# power.net
KiCad netlist of a schematic drawn in Altium Designer
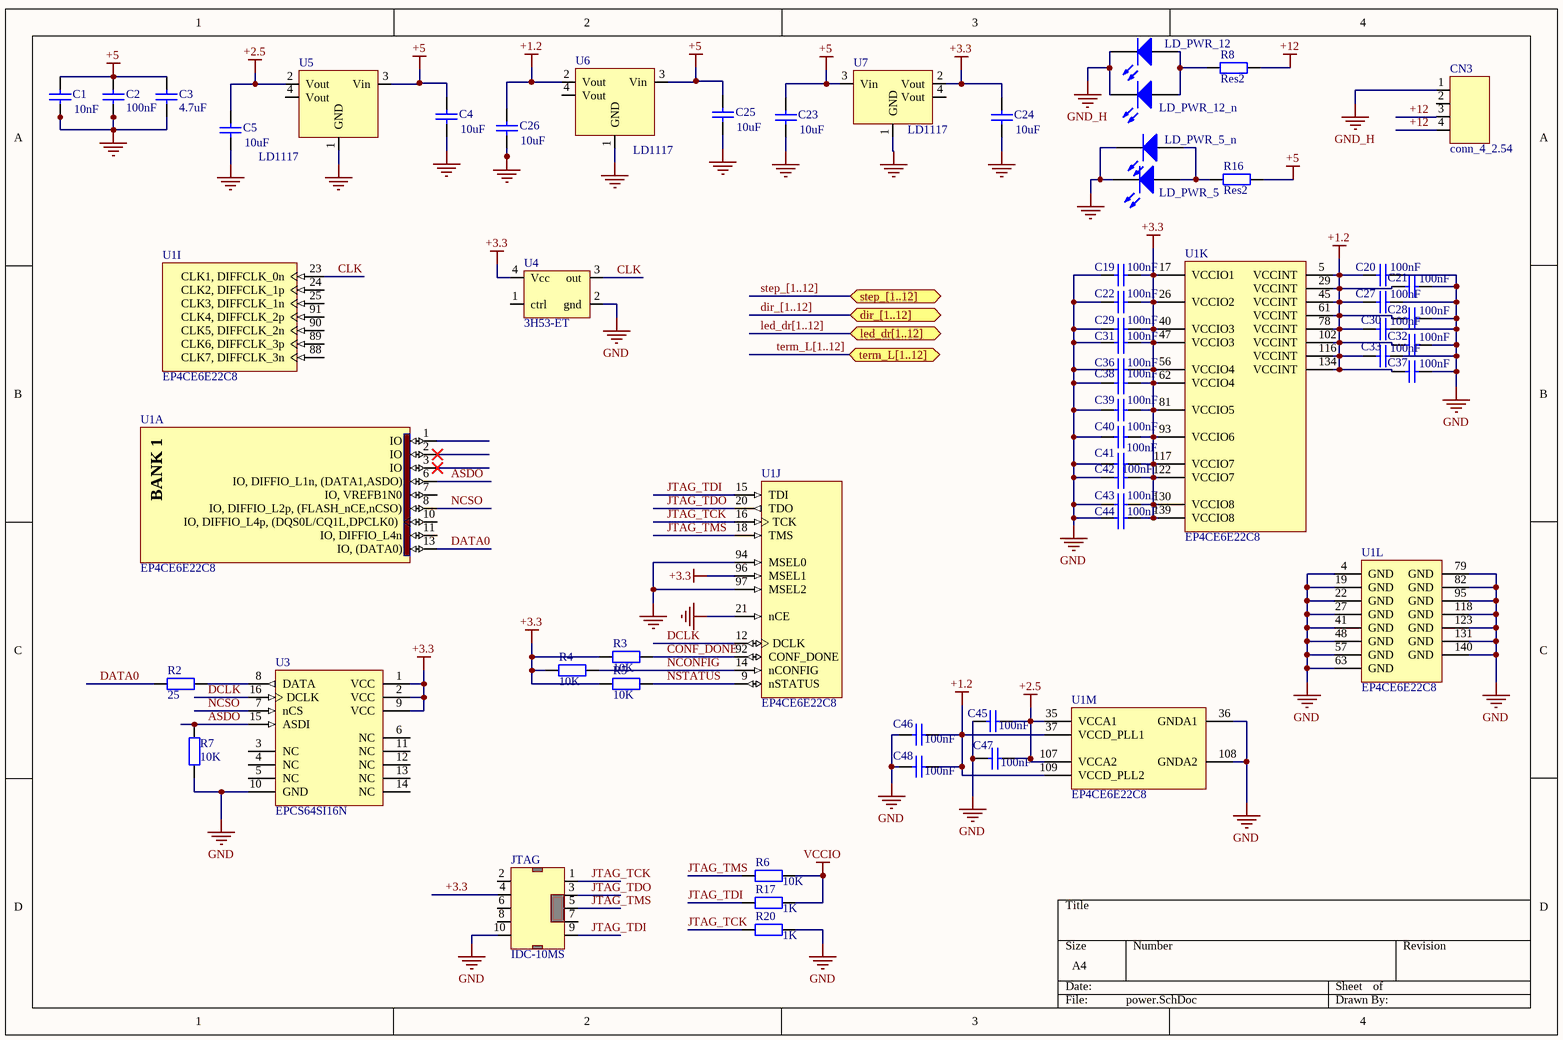
[diagram p0: power.SchDoc]

(export (version "E")
  (design (tool "Eeschema 10.0.6"))
  (components
    (comp (ref "C1")
      (value "10nF")
      (footprint "CAPC1608M")
      (description "Capacitor")
      (fields (field (name "Comment") "Cap") (field (name "PUBLISHER") "Altium Limited"))
      (libsource (lib "Miscellaneous Devices") (part "Cap"))
    )
    (comp (ref "C2")
      (value "100nF")
      (footprint "CAPC1608M")
      (description "Capacitor")
      (fields (field (name "Comment") "Cap") (field (name "PUBLISHER") "Altium Limited"))
      (libsource (lib "Miscellaneous Devices") (part "Cap"))
    )
    (comp (ref "C3")
      (value "4.7uF")
      (footprint "CAPC1608M")
      (description "Capacitor")
      (fields (field (name "Comment") "Cap") (field (name "PUBLISHER") "Altium Limited"))
      (libsource (lib "Miscellaneous Devices") (part "Cap"))
    )
    (comp (ref "C4")
      (value "10uF")
      (footprint "CAPC2012M")
      (description "Capacitor")
      (fields (field (name "Comment") "Cap") (field (name "PUBLISHER") "Altium Limited"))
      (libsource (lib "Miscellaneous Devices") (part "Cap"))
    )
    (comp (ref "C5")
      (value "10uF")
      (footprint "CAPC2012M")
      (description "Capacitor")
      (fields (field (name "Comment") "Cap") (field (name "PUBLISHER") "Altium Limited"))
      (libsource (lib "Miscellaneous Devices") (part "Cap"))
    )
    (comp (ref "C19")
      (value "100nF")
      (footprint "CAPC1608M")
      (description "Capacitor")
      (fields (field (name "Comment") "Cap") (field (name "PUBLISHER") "Altium Limited"))
      (libsource (lib "Miscellaneous Devices") (part "Cap"))
    )
    (comp (ref "C20")
      (value "100nF")
      (footprint "CAPC1608M")
      (description "Capacitor")
      (fields (field (name "Comment") "Cap") (field (name "PUBLISHER") "Altium Limited"))
      (libsource (lib "Miscellaneous Devices") (part "Cap"))
    )
    (comp (ref "C21")
      (value "100nF")
      (footprint "CAPC1608M")
      (description "Capacitor")
      (fields (field (name "Comment") "Cap") (field (name "PUBLISHER") "Altium Limited"))
      (libsource (lib "Miscellaneous Devices") (part "Cap"))
    )
    (comp (ref "C22")
      (value "100nF")
      (footprint "CAPC1608M")
      (description "Capacitor")
      (fields (field (name "Comment") "Cap") (field (name "PUBLISHER") "Altium Limited"))
      (libsource (lib "Miscellaneous Devices") (part "Cap"))
    )
    (comp (ref "C23")
      (value "10uF")
      (footprint "CAPC2012M")
      (description "Capacitor")
      (fields (field (name "Comment") "Cap") (field (name "PUBLISHER") "Altium Limited"))
      (libsource (lib "Miscellaneous Devices") (part "Cap"))
    )
    (comp (ref "C24")
      (value "10uF")
      (footprint "CAPC2012M")
      (description "Capacitor")
      (fields (field (name "Comment") "Cap") (field (name "PUBLISHER") "Altium Limited"))
      (libsource (lib "Miscellaneous Devices") (part "Cap"))
    )
    (comp (ref "C25")
      (value "10uF")
      (footprint "CAPC2012M")
      (description "Capacitor")
      (fields (field (name "Comment") "Cap") (field (name "PUBLISHER") "Altium Limited"))
      (libsource (lib "Miscellaneous Devices") (part "Cap"))
    )
    (comp (ref "C26")
      (value "10uF")
      (footprint "CAPC2012M")
      (description "Capacitor")
      (fields (field (name "Comment") "Cap") (field (name "PUBLISHER") "Altium Limited"))
      (libsource (lib "Miscellaneous Devices") (part "Cap"))
    )
    (comp (ref "C27")
      (value "100nF")
      (footprint "CAPC1608M")
      (description "Capacitor")
      (fields (field (name "Comment") "Cap") (field (name "PUBLISHER") "Altium Limited"))
      (libsource (lib "Miscellaneous Devices") (part "Cap"))
    )
    (comp (ref "C28")
      (value "100nF")
      (footprint "CAPC1608M")
      (description "Capacitor")
      (fields (field (name "Comment") "Cap") (field (name "PUBLISHER") "Altium Limited"))
      (libsource (lib "Miscellaneous Devices") (part "Cap"))
    )
    (comp (ref "C29")
      (value "100nF")
      (footprint "CAPC1608M")
      (description "Capacitor")
      (fields (field (name "Comment") "Cap") (field (name "PUBLISHER") "Altium Limited"))
      (libsource (lib "Miscellaneous Devices") (part "Cap"))
    )
    (comp (ref "C30")
      (value "100nF")
      (footprint "CAPC1608M")
      (description "Capacitor")
      (fields (field (name "Comment") "Cap") (field (name "PUBLISHER") "Altium Limited"))
      (libsource (lib "Miscellaneous Devices") (part "Cap"))
    )
    (comp (ref "C31")
      (value "100nF")
      (footprint "CAPC1608M")
      (description "Capacitor")
      (fields (field (name "Comment") "Cap") (field (name "PUBLISHER") "Altium Limited"))
      (libsource (lib "Miscellaneous Devices") (part "Cap"))
    )
    (comp (ref "C32")
      (value "100nF")
      (footprint "CAPC1608M")
      (description "Capacitor")
      (fields (field (name "Comment") "Cap") (field (name "PUBLISHER") "Altium Limited"))
      (libsource (lib "Miscellaneous Devices") (part "Cap"))
    )
    (comp (ref "C33")
      (value "100nF")
      (footprint "CAPC1608M")
      (description "Capacitor")
      (fields (field (name "Comment") "Cap") (field (name "PUBLISHER") "Altium Limited"))
      (libsource (lib "Miscellaneous Devices") (part "Cap"))
    )
    (comp (ref "C36")
      (value "100nF")
      (footprint "CAPC1608M")
      (description "Capacitor")
      (fields (field (name "Comment") "Cap") (field (name "PUBLISHER") "Altium Limited"))
      (libsource (lib "Miscellaneous Devices") (part "Cap"))
    )
    (comp (ref "C37")
      (value "100nF")
      (footprint "CAPC1608M")
      (description "Capacitor")
      (fields (field (name "Comment") "Cap") (field (name "PUBLISHER") "Altium Limited"))
      (libsource (lib "Miscellaneous Devices") (part "Cap"))
    )
    (comp (ref "C38")
      (value "100nF")
      (footprint "CAPC1608M")
      (description "Capacitor")
      (fields (field (name "Comment") "Cap") (field (name "PUBLISHER") "Altium Limited"))
      (libsource (lib "Miscellaneous Devices") (part "Cap"))
    )
    (comp (ref "C39")
      (value "100nF")
      (footprint "CAPC1608M")
      (description "Capacitor")
      (fields (field (name "Comment") "Cap") (field (name "PUBLISHER") "Altium Limited"))
      (libsource (lib "Miscellaneous Devices") (part "Cap"))
    )
    (comp (ref "C40")
      (value "100nF")
      (footprint "CAPC1608M")
      (description "Capacitor")
      (fields (field (name "Comment") "Cap") (field (name "PUBLISHER") "Altium Limited"))
      (libsource (lib "Miscellaneous Devices") (part "Cap"))
    )
    (comp (ref "C41")
      (value "100nF")
      (footprint "CAPC1608M")
      (description "Capacitor")
      (fields (field (name "Comment") "Cap") (field (name "PUBLISHER") "Altium Limited"))
      (libsource (lib "Miscellaneous Devices") (part "Cap"))
    )
    (comp (ref "C42")
      (value "100nF")
      (footprint "CAPC1608M")
      (description "Capacitor")
      (fields (field (name "Comment") "Cap") (field (name "PUBLISHER") "Altium Limited"))
      (libsource (lib "Miscellaneous Devices") (part "Cap"))
    )
    (comp (ref "C43")
      (value "100nF")
      (footprint "CAPC1608M")
      (description "Capacitor")
      (fields (field (name "Comment") "Cap") (field (name "PUBLISHER") "Altium Limited"))
      (libsource (lib "Miscellaneous Devices") (part "Cap"))
    )
    (comp (ref "C44")
      (value "100nF")
      (footprint "CAPC1608M")
      (description "Capacitor")
      (fields (field (name "Comment") "Cap") (field (name "PUBLISHER") "Altium Limited"))
      (libsource (lib "Miscellaneous Devices") (part "Cap"))
    )
    (comp (ref "C45")
      (value "100nF")
      (footprint "CAPC1608M")
      (description "Capacitor")
      (fields (field (name "Comment") "Cap") (field (name "PUBLISHER") "Altium Limited"))
      (libsource (lib "Miscellaneous Devices") (part "Cap"))
    )
    (comp (ref "C46")
      (value "100nF")
      (footprint "CAPC1608M")
      (description "Capacitor")
      (fields (field (name "Comment") "Cap") (field (name "PUBLISHER") "Altium Limited"))
      (libsource (lib "Miscellaneous Devices") (part "Cap"))
    )
    (comp (ref "C47")
      (value "100nF")
      (footprint "CAPC1608M")
      (description "Capacitor")
      (fields (field (name "Comment") "Cap") (field (name "PUBLISHER") "Altium Limited"))
      (libsource (lib "Miscellaneous Devices") (part "Cap"))
    )
    (comp (ref "C48")
      (value "100nF")
      (footprint "CAPC1608M")
      (description "Capacitor")
      (fields (field (name "Comment") "Cap") (field (name "PUBLISHER") "Altium Limited"))
      (libsource (lib "Miscellaneous Devices") (part "Cap"))
    )
    (comp (ref "CN3")
      (value "conn_4_2.54")
      (footprint "SCKT/SM4.5-2H4")
      (libsource (lib "Schlib1") (part "conn_4_2.54"))
    )
    (comp (ref "JTAG")
      (value "IDC-10MS")
      (footprint "IDC2.54-V10D")
      (description "BH-10(IDC-10MS)")
      (libsource (lib "IDC") (part "BH-10(IDC-10MS)"))
    )
    (comp (ref "LD_PWR_5")
      (value "led")
      (footprint "RESC2012M")
      (description "chip led")
      (libsource (lib "Schlib1") (part "chip led"))
    )
    (comp (ref "LD_PWR_5_n")
      (value "led")
      (footprint "led-pins")
      (description "chip led")
      (libsource (lib "Schlib1") (part "chip led"))
    )
    (comp (ref "LD_PWR_12")
      (value "led")
      (footprint "RESC2012M")
      (description "chip led")
      (libsource (lib "Schlib1") (part "chip led"))
    )
    (comp (ref "LD_PWR_12_n")
      (value "led")
      (footprint "led-pins")
      (description "chip led")
      (libsource (lib "Schlib1") (part "chip led"))
    )
    (comp (ref "R2")
      (value "25")
      (footprint "RESC2012M")
      (description "Resistor")
      (fields (field (name "PUBLISHER") "Altium Limited"))
      (libsource (lib "Miscellaneous Devices") (part "Res2"))
    )
    (comp (ref "R3")
      (value "10K")
      (footprint "RESC2012M")
      (description "Resistor")
      (fields (field (name "PUBLISHER") "Altium Limited"))
      (libsource (lib "Miscellaneous Devices") (part "Res2"))
    )
    (comp (ref "R4")
      (value "10K")
      (footprint "RESC2012M")
      (description "Resistor")
      (fields (field (name "PUBLISHER") "Altium Limited"))
      (libsource (lib "Miscellaneous Devices") (part "Res2"))
    )
    (comp (ref "R5")
      (value "10K")
      (footprint "RESC2012M")
      (description "Resistor")
      (fields (field (name "PUBLISHER") "Altium Limited"))
      (libsource (lib "Miscellaneous Devices") (part "Res2"))
    )
    (comp (ref "R6")
      (value "10K")
      (footprint "RESC2012M")
      (description "Resistor")
      (fields (field (name "PUBLISHER") "Altium Limited"))
      (libsource (lib "Miscellaneous Devices") (part "Res2"))
    )
    (comp (ref "R7")
      (value "10K")
      (footprint "RESC2012M")
      (description "Resistor")
      (fields (field (name "Comment") "Res2") (field (name "PUBLISHER") "Altium Limited"))
      (libsource (lib "Miscellaneous Devices") (part "Res2"))
    )
    (comp (ref "R8")
      (value "Res2")
      (footprint "RESC2012M")
      (description "Resistor")
      (fields (field (name "PUBLISHER") "Altium Limited"))
      (libsource (lib "Miscellaneous Devices") (part "Res2"))
    )
    (comp (ref "R16")
      (value "Res2")
      (footprint "RESC2012M")
      (description "Resistor")
      (fields (field (name "PUBLISHER") "Altium Limited"))
      (libsource (lib "Miscellaneous Devices") (part "Res2"))
    )
    (comp (ref "R17")
      (value "1K")
      (footprint "RESC2012M")
      (description "Resistor")
      (fields (field (name "PUBLISHER") "Altium Limited"))
      (libsource (lib "Miscellaneous Devices") (part "Res2"))
    )
    (comp (ref "R20")
      (value "1K")
      (footprint "RESC2012M")
      (description "Resistor")
      (fields (field (name "PUBLISHER") "Altium Limited"))
      (libsource (lib "Miscellaneous Devices") (part "Res2"))
    )
    (comp (ref "U1")
      (value "EP4CE6E22C8")
      (footprint "EQFP144_M")
      (description "Cyclone IV Family FPGA, 2V Core, 91 I/O Pins, 2 PLLs, 144-Pin QFP, Speed Grade 8, Commercial Grade")
      (fields (field (name "PUBLISHER") "Altium Limited"))
      (libsource (lib "Altera Cyclone IV E") (part "EP4CE6E22C8"))
    )
    (comp (ref "U3")
      (value "EPCS64SI16N")
      (footprint "SOIC16_M")
      (fields (field (name "PUBLISHER") "Altium Limited"))
      (libsource (lib "Altera EPCS Configuration Device") (part "EPCS64SI16N"))
    )
    (comp (ref "U4")
      (value "3H53-ET")
      (footprint "2SMX-3SMXB")
      (description "Кварцевый генератор")
      (libsource (lib "Schlib1") (part "3H53-ET"))
    )
    (comp (ref "U5")
      (value "LD1117")
      (footprint "SOT223-4M")
      (description "st LD1086D2T")
      (libsource (lib "Schlib1") (part "LD1086D2T"))
    )
    (comp (ref "U6")
      (value "LD1117")
      (footprint "SOT223-4M")
      (description "st LD1086D2T")
      (libsource (lib "Schlib1") (part "LD1086D2T"))
    )
    (comp (ref "U7")
      (value "LD1117")
      (footprint "SOT223-4M")
      (description "ADP3339AKCZ-3.3-R7")
      (libsource (lib "Schlib1") (part "ADP3339"))
    )
  )
  (nets
    (net (code "49") (name "+1.2") (class "Default")
      (node (ref "C20") (pin "1") (pinfunction "1_1") (pintype "passive"))
      (node (ref "C21") (pin "1") (pinfunction "1_1") (pintype "passive"))
      (node (ref "C26") (pin "1") (pinfunction "1_1") (pintype "passive"))
      (node (ref "C27") (pin "1") (pinfunction "1_1") (pintype "passive"))
      (node (ref "C28") (pin "1") (pinfunction "1_1") (pintype "passive"))
      (node (ref "C30") (pin "1") (pinfunction "1_1") (pintype "passive"))
      (node (ref "C32") (pin "1") (pinfunction "1_1") (pintype "passive"))
      (node (ref "C33") (pin "1") (pinfunction "1_1") (pintype "passive"))
      (node (ref "C37") (pin "1") (pinfunction "1_1") (pintype "passive"))
      (node (ref "C46") (pin "2") (pinfunction "2_2") (pintype "passive"))
      (node (ref "C48") (pin "2") (pinfunction "2_2") (pintype "passive"))
      (node (ref "U1") (pin "102") (pinfunction "VCCINT_102") (pintype "power_in"))
      (node (ref "U1") (pin "109") (pinfunction "VCCD_PLL2_109") (pintype "power_in"))
      (node (ref "U1") (pin "116") (pinfunction "VCCINT_116") (pintype "power_in"))
      (node (ref "U1") (pin "134") (pinfunction "VCCINT_134") (pintype "power_in"))
      (node (ref "U1") (pin "29") (pinfunction "VCCINT_29") (pintype "power_in"))
      (node (ref "U1") (pin "37") (pinfunction "VCCD_PLL1_37") (pintype "power_in"))
      (node (ref "U1") (pin "45") (pinfunction "VCCINT_45") (pintype "power_in"))
      (node (ref "U1") (pin "5") (pinfunction "VCCINT_5") (pintype "power_in"))
      (node (ref "U1") (pin "61") (pinfunction "VCCINT_61") (pintype "power_in"))
      (node (ref "U1") (pin "78") (pinfunction "VCCINT_78") (pintype "power_in"))
      (node (ref "U6") (pin "2") (pinfunction "Vout_2") (pintype "passive"))
    )
    (net (code "50") (name "+2.5") (class "Default")
      (node (ref "C45") (pin "2") (pinfunction "2_2") (pintype "passive"))
      (node (ref "C47") (pin "2") (pinfunction "2_2") (pintype "passive"))
      (node (ref "C5") (pin "1") (pinfunction "1_1") (pintype "passive"))
      (node (ref "U1") (pin "107") (pinfunction "VCCA2_107") (pintype "power_in"))
      (node (ref "U1") (pin "35") (pinfunction "VCCA1_35") (pintype "power_in"))
      (node (ref "U5") (pin "2") (pinfunction "Vout_2") (pintype "passive"))
    )
    (net (code "51") (name "+3.3") (class "Default")
      (node (ref "C19") (pin "2") (pinfunction "2_2") (pintype "passive"))
      (node (ref "C22") (pin "2") (pinfunction "2_2") (pintype "passive"))
      (node (ref "C24") (pin "1") (pinfunction "1_1") (pintype "passive"))
      (node (ref "C29") (pin "2") (pinfunction "2_2") (pintype "passive"))
      (node (ref "C31") (pin "2") (pinfunction "2_2") (pintype "passive"))
      (node (ref "C36") (pin "2") (pinfunction "2_2") (pintype "passive"))
      (node (ref "C38") (pin "2") (pinfunction "2_2") (pintype "passive"))
      (node (ref "C39") (pin "2") (pinfunction "2_2") (pintype "passive"))
      (node (ref "C40") (pin "2") (pinfunction "2_2") (pintype "passive"))
      (node (ref "C41") (pin "2") (pinfunction "2_2") (pintype "passive"))
      (node (ref "C42") (pin "2") (pinfunction "2_2") (pintype "passive"))
      (node (ref "C43") (pin "2") (pinfunction "2_2") (pintype "passive"))
      (node (ref "C44") (pin "2") (pinfunction "2_2") (pintype "passive"))
      (node (ref "JTAG") (pin "4") (pintype "passive"))
      (node (ref "R3") (pin "1") (pinfunction "1_1") (pintype "passive"))
      (node (ref "R4") (pin "1") (pinfunction "1_1") (pintype "passive"))
      (node (ref "R5") (pin "1") (pinfunction "1_1") (pintype "passive"))
      (node (ref "U1") (pin "117") (pinfunction "VCCIO7_117") (pintype "power_in"))
      (node (ref "U1") (pin "122") (pinfunction "VCCIO7_122") (pintype "power_in"))
      (node (ref "U1") (pin "130") (pinfunction "VCCIO8_130") (pintype "power_in"))
      (node (ref "U1") (pin "139") (pinfunction "VCCIO8_139") (pintype "power_in"))
      (node (ref "U1") (pin "17") (pinfunction "VCCIO1_17") (pintype "power_in"))
      (node (ref "U1") (pin "26") (pinfunction "VCCIO2_26") (pintype "power_in"))
      (node (ref "U1") (pin "40") (pinfunction "VCCIO3_40") (pintype "power_in"))
      (node (ref "U1") (pin "47") (pinfunction "VCCIO3_47") (pintype "power_in"))
      (node (ref "U1") (pin "56") (pinfunction "VCCIO4_56") (pintype "power_in"))
      (node (ref "U1") (pin "62") (pinfunction "VCCIO4_62") (pintype "power_in"))
      (node (ref "U1") (pin "81") (pinfunction "VCCIO5_81") (pintype "power_in"))
      (node (ref "U1") (pin "93") (pinfunction "VCCIO6_93") (pintype "power_in"))
      (node (ref "U1") (pin "96") (pinfunction "MSEL1_96") (pintype "input"))
      (node (ref "U3") (pin "1") (pinfunction "VCC_1") (pintype "power_in"))
      (node (ref "U3") (pin "2") (pinfunction "VCC_2") (pintype "power_in"))
      (node (ref "U3") (pin "9") (pinfunction "VCC_9") (pintype "power_in"))
      (node (ref "U4") (pin "4") (pinfunction "Vcc_4") (pintype "passive"))
      (node (ref "U7") (pin "2") (pinfunction "Vout_2") (pintype "power_in"))
    )
    (net (code "52") (name "+5") (class "Default")
      (node (ref "C1") (pin "1") (pinfunction "1_1") (pintype "passive"))
      (node (ref "C2") (pin "1") (pinfunction "1_1") (pintype "passive"))
      (node (ref "C23") (pin "1") (pinfunction "1_1") (pintype "passive"))
      (node (ref "C25") (pin "1") (pinfunction "1_1") (pintype "passive"))
      (node (ref "C3") (pin "1") (pinfunction "1_1") (pintype "passive"))
      (node (ref "C4") (pin "1") (pinfunction "1_1") (pintype "passive"))
      (node (ref "R16") (pin "2") (pinfunction "2_2") (pintype "passive"))
      (node (ref "U5") (pin "3") (pinfunction "Vin_3") (pintype "passive"))
      (node (ref "U6") (pin "3") (pinfunction "Vin_3") (pintype "passive"))
      (node (ref "U7") (pin "3") (pinfunction "Vin_3") (pintype "power_in"))
    )
    (net (code "53") (name "+12") (class "Default")
      (node (ref "CN3") (pin "3") (pintype "passive"))
      (node (ref "CN3") (pin "4") (pintype "passive"))
      (node (ref "R8") (pin "2") (pinfunction "2_2") (pintype "passive"))
    )
    (net (code "54") (name "/ASDO") (class "Default")
      (node (ref "R7") (pin "2") (pinfunction "2_2") (pintype "passive"))
      (node (ref "U1") (pin "6") (pinfunction "IO,_DIFFIO_L1n,_(DATA1,ASDO)_6") (pintype "bidirectional"))
      (node (ref "U3") (pin "15") (pinfunction "ASDI_15") (pintype "input"))
    )
    (net (code "55") (name "/CLK") (class "Default")
      (node (ref "U1") (pin "23") (pinfunction "CLK1,_DIFFCLK_0n_23") (pintype "input"))
      (node (ref "U4") (pin "3") (pinfunction "out_3") (pintype "passive"))
    )
    (net (code "56") (name "/CONF_DONE") (class "Default")
      (node (ref "R3") (pin "2") (pinfunction "2_2") (pintype "passive"))
      (node (ref "U1") (pin "92") (pinfunction "CONF_DONE_92") (pintype "bidirectional"))
    )
    (net (code "57") (name "/DATA0") (class "Default")
      (node (ref "R2") (pin "1") (pinfunction "1_1") (pintype "passive"))
      (node (ref "U1") (pin "13") (pinfunction "IO,_(DATA0)_13") (pintype "bidirectional"))
    )
    (net (code "58") (name "/DCLK") (class "Default")
      (node (ref "U1") (pin "12") (pinfunction "DCLK_12") (pintype "bidirectional"))
      (node (ref "U3") (pin "16") (pinfunction "DCLK_16") (pintype "input"))
    )
    (net (code "59") (name "/JTAG_TCK") (class "Default")
      (node (ref "JTAG") (pin "1") (pintype "passive"))
      (node (ref "R20") (pin "1") (pinfunction "1_1") (pintype "passive"))
      (node (ref "U1") (pin "16") (pinfunction "TCK_16") (pintype "input"))
    )
    (net (code "60") (name "/JTAG_TDI") (class "Default")
      (node (ref "JTAG") (pin "9") (pintype "passive"))
      (node (ref "R17") (pin "1") (pinfunction "1_1") (pintype "passive"))
      (node (ref "U1") (pin "15") (pinfunction "TDI_15") (pintype "input"))
    )
    (net (code "61") (name "/JTAG_TDO") (class "Default")
      (node (ref "JTAG") (pin "3") (pintype "passive"))
      (node (ref "U1") (pin "20") (pinfunction "TDO_20") (pintype "output"))
    )
    (net (code "62") (name "/JTAG_TMS") (class "Default")
      (node (ref "JTAG") (pin "5") (pintype "passive"))
      (node (ref "R6") (pin "1") (pinfunction "1_1") (pintype "passive"))
      (node (ref "U1") (pin "18") (pinfunction "TMS_18") (pintype "input"))
    )
    (net (code "63") (name "/NCONFIG") (class "Default")
      (node (ref "R4") (pin "2") (pinfunction "2_2") (pintype "passive"))
      (node (ref "U1") (pin "14") (pinfunction "nCONFIG_14") (pintype "input"))
    )
    (net (code "64") (name "/NCSO") (class "Default")
      (node (ref "U1") (pin "8") (pinfunction "IO,_DIFFIO_L2p,_(FLASH_nCE,nCSO)_8") (pintype "bidirectional"))
      (node (ref "U3") (pin "7") (pinfunction "nCS_7") (pintype "input"))
    )
    (net (code "65") (name "/NSTATUS") (class "Default")
      (node (ref "R5") (pin "2") (pinfunction "2_2") (pintype "passive"))
      (node (ref "U1") (pin "9") (pinfunction "nSTATUS_9") (pintype "bidirectional"))
    )
    (net (code "70") (name "GND") (class "Default")
      (node (ref "C1") (pin "2") (pinfunction "2_2") (pintype "passive"))
      (node (ref "C19") (pin "1") (pinfunction "1_1") (pintype "passive"))
      (node (ref "C2") (pin "2") (pinfunction "2_2") (pintype "passive"))
      (node (ref "C20") (pin "2") (pinfunction "2_2") (pintype "passive"))
      (node (ref "C21") (pin "2") (pinfunction "2_2") (pintype "passive"))
      (node (ref "C22") (pin "1") (pinfunction "1_1") (pintype "passive"))
      (node (ref "C23") (pin "2") (pinfunction "2_2") (pintype "passive"))
      (node (ref "C24") (pin "2") (pinfunction "2_2") (pintype "passive"))
      (node (ref "C25") (pin "2") (pinfunction "2_2") (pintype "passive"))
      (node (ref "C26") (pin "2") (pinfunction "2_2") (pintype "passive"))
      (node (ref "C27") (pin "2") (pinfunction "2_2") (pintype "passive"))
      (node (ref "C28") (pin "2") (pinfunction "2_2") (pintype "passive"))
      (node (ref "C29") (pin "1") (pinfunction "1_1") (pintype "passive"))
      (node (ref "C3") (pin "2") (pinfunction "2_2") (pintype "passive"))
      (node (ref "C30") (pin "2") (pinfunction "2_2") (pintype "passive"))
      (node (ref "C31") (pin "1") (pinfunction "1_1") (pintype "passive"))
      (node (ref "C32") (pin "2") (pinfunction "2_2") (pintype "passive"))
      (node (ref "C33") (pin "2") (pinfunction "2_2") (pintype "passive"))
      (node (ref "C36") (pin "1") (pinfunction "1_1") (pintype "passive"))
      (node (ref "C37") (pin "2") (pinfunction "2_2") (pintype "passive"))
      (node (ref "C38") (pin "1") (pinfunction "1_1") (pintype "passive"))
      (node (ref "C39") (pin "1") (pinfunction "1_1") (pintype "passive"))
      (node (ref "C4") (pin "2") (pinfunction "2_2") (pintype "passive"))
      (node (ref "C40") (pin "1") (pinfunction "1_1") (pintype "passive"))
      (node (ref "C41") (pin "1") (pinfunction "1_1") (pintype "passive"))
      (node (ref "C42") (pin "1") (pinfunction "1_1") (pintype "passive"))
      (node (ref "C43") (pin "1") (pinfunction "1_1") (pintype "passive"))
      (node (ref "C44") (pin "1") (pinfunction "1_1") (pintype "passive"))
      (node (ref "C45") (pin "1") (pinfunction "1_1") (pintype "passive"))
      (node (ref "C46") (pin "1") (pinfunction "1_1") (pintype "passive"))
      (node (ref "C47") (pin "1") (pinfunction "1_1") (pintype "passive"))
      (node (ref "C48") (pin "1") (pinfunction "1_1") (pintype "passive"))
      (node (ref "C5") (pin "2") (pinfunction "2_2") (pintype "passive"))
      (node (ref "JTAG") (pin "10") (pintype "passive"))
      (node (ref "LD_PWR_5") (pin "2") (pinfunction "K_2") (pintype "passive"))
      (node (ref "LD_PWR_5_n") (pin "2") (pinfunction "K_2") (pintype "passive"))
      (node (ref "R20") (pin "2") (pinfunction "2_2") (pintype "passive"))
      (node (ref "R7") (pin "1") (pinfunction "1_1") (pintype "passive"))
      (node (ref "U1") (pin "108") (pinfunction "GNDA2_108") (pintype "power_in"))
      (node (ref "U1") (pin "118") (pinfunction "GND_118") (pintype "power_in"))
      (node (ref "U1") (pin "123") (pinfunction "GND_123") (pintype "power_in"))
      (node (ref "U1") (pin "131") (pinfunction "GND_131") (pintype "power_in"))
      (node (ref "U1") (pin "140") (pinfunction "GND_140") (pintype "power_in"))
      (node (ref "U1") (pin "19") (pinfunction "GND_19") (pintype "power_in"))
      (node (ref "U1") (pin "21") (pinfunction "nCE_21") (pintype "input"))
      (node (ref "U1") (pin "22") (pinfunction "GND_22") (pintype "power_in"))
      (node (ref "U1") (pin "27") (pinfunction "GND_27") (pintype "power_in"))
      (node (ref "U1") (pin "36") (pinfunction "GNDA1_36") (pintype "power_in"))
      (node (ref "U1") (pin "4") (pinfunction "GND_4") (pintype "power_in"))
      (node (ref "U1") (pin "41") (pinfunction "GND_41") (pintype "power_in"))
      (node (ref "U1") (pin "48") (pinfunction "GND_48") (pintype "power_in"))
      (node (ref "U1") (pin "57") (pinfunction "GND_57") (pintype "power_in"))
      (node (ref "U1") (pin "63") (pinfunction "GND_63") (pintype "power_in"))
      (node (ref "U1") (pin "79") (pinfunction "GND_79") (pintype "power_in"))
      (node (ref "U1") (pin "82") (pinfunction "GND_82") (pintype "power_in"))
      (node (ref "U1") (pin "94") (pinfunction "MSEL0_94") (pintype "input"))
      (node (ref "U1") (pin "95") (pinfunction "GND_95") (pintype "power_in"))
      (node (ref "U1") (pin "97") (pinfunction "MSEL2_97") (pintype "input"))
      (node (ref "U3") (pin "10") (pinfunction "GND_10") (pintype "power_in"))
      (node (ref "U4") (pin "2") (pinfunction "gnd_2") (pintype "passive"))
      (node (ref "U5") (pin "1") (pinfunction "GND_1") (pintype "passive"))
      (node (ref "U6") (pin "1") (pinfunction "GND_1") (pintype "passive"))
      (node (ref "U7") (pin "1") (pinfunction "GND_1") (pintype "power_in"))
    )
    (net (code "71") (name "GND_H") (class "Default")
      (node (ref "CN3") (pin "1") (pintype "passive"))
      (node (ref "LD_PWR_12") (pin "2") (pinfunction "K_2") (pintype "passive"))
      (node (ref "LD_PWR_12_n") (pin "2") (pinfunction "K_2") (pintype "passive"))
    )
    (net (code "72") (name "Net-(LD_PWR_5-A)") (class "Default")
      (node (ref "LD_PWR_5") (pin "1") (pinfunction "A_1") (pintype "passive"))
      (node (ref "LD_PWR_5_n") (pin "1") (pinfunction "A_1") (pintype "passive"))
      (node (ref "R16") (pin "1") (pinfunction "1_1") (pintype "passive"))
    )
    (net (code "73") (name "Net-(LD_PWR_12-A)") (class "Default")
      (node (ref "LD_PWR_12") (pin "1") (pinfunction "A_1") (pintype "passive"))
      (node (ref "LD_PWR_12_n") (pin "1") (pinfunction "A_1") (pintype "passive"))
      (node (ref "R8") (pin "1") (pinfunction "1_1") (pintype "passive"))
    )
    (net (code "74") (name "Net-(U3-DATA)") (class "Default")
      (node (ref "R2") (pin "2") (pinfunction "2_2") (pintype "passive"))
      (node (ref "U3") (pin "8") (pinfunction "DATA_8") (pintype "output"))
    )
    (net (code "75") (name "VCCIO") (class "Default")
      (node (ref "R17") (pin "2") (pinfunction "2_2") (pintype "passive"))
      (node (ref "R6") (pin "2") (pinfunction "2_2") (pintype "passive"))
    )
    (net (code "76") (name "unconnected-(CN3-Pad2)") (class "Default")
      (node (ref "CN3") (pin "2") (pintype "passive"))
    )
    (net (code "77") (name "unconnected-(JTAG-Pad2)") (class "Default")
      (node (ref "JTAG") (pin "2") (pintype "passive"))
    )
    (net (code "78") (name "unconnected-(JTAG-Pad6)") (class "Default")
      (node (ref "JTAG") (pin "6") (pintype "passive"))
    )
    (net (code "79") (name "unconnected-(JTAG-Pad7)") (class "Default")
      (node (ref "JTAG") (pin "7") (pintype "passive"))
    )
    (net (code "80") (name "unconnected-(JTAG-Pad8)") (class "Default")
      (node (ref "JTAG") (pin "8") (pintype "passive"))
    )
    (net (code "81") (name "unconnected-(U1A-IO,_DIFFIO_L4n-Pad11)") (class "Default")
      (node (ref "U1") (pin "11") (pinfunction "IO,_DIFFIO_L4n_11") (pintype "bidirectional"))
    )
    (net (code "82") (name "unconnected-(U1A-IO,_DIFFIO_L4p,_(DQS0L{slash}CQ1L,DPCLK0)-Pad10)") (class "Default")
      (node (ref "U1") (pin "10") (pinfunction "IO,_DIFFIO_L4p,_(DQS0L/CQ1L,DPCLK0)_10") (pintype "bidirectional"))
    )
    (net (code "83") (name "unconnected-(U1A-IO,_VREFB1N0-Pad7)") (class "Default")
      (node (ref "U1") (pin "7") (pinfunction "IO,_VREFB1N0_7") (pintype "bidirectional"))
    )
    (net (code "84") (name "unconnected-(U1A-IO-Pad1)") (class "Default")
      (node (ref "U1") (pin "1") (pinfunction "IO_1") (pintype "bidirectional"))
    )
    (net (code "85") (name "unconnected-(U1A-IO-Pad2)") (class "Default")
      (node (ref "U1") (pin "2") (pinfunction "IO_2") (pintype "bidirectional+no_connect"))
    )
    (net (code "86") (name "unconnected-(U1A-IO-Pad3)") (class "Default")
      (node (ref "U1") (pin "3") (pinfunction "IO_3") (pintype "bidirectional+no_connect"))
    )
    (net (code "87") (name "unconnected-(U1I-CLK2,_DIFFCLK_1p-Pad24)") (class "Default")
      (node (ref "U1") (pin "24") (pinfunction "CLK2,_DIFFCLK_1p_24") (pintype "input"))
    )
    (net (code "88") (name "unconnected-(U1I-CLK3,_DIFFCLK_1n-Pad25)") (class "Default")
      (node (ref "U1") (pin "25") (pinfunction "CLK3,_DIFFCLK_1n_25") (pintype "input"))
    )
    (net (code "89") (name "unconnected-(U1I-CLK4,_DIFFCLK_2p-Pad91)") (class "Default")
      (node (ref "U1") (pin "91") (pinfunction "CLK4,_DIFFCLK_2p_91") (pintype "input"))
    )
    (net (code "90") (name "unconnected-(U1I-CLK5,_DIFFCLK_2n-Pad90)") (class "Default")
      (node (ref "U1") (pin "90") (pinfunction "CLK5,_DIFFCLK_2n_90") (pintype "input"))
    )
    (net (code "91") (name "unconnected-(U1I-CLK6,_DIFFCLK_3p-Pad89)") (class "Default")
      (node (ref "U1") (pin "89") (pinfunction "CLK6,_DIFFCLK_3p_89") (pintype "input"))
    )
    (net (code "92") (name "unconnected-(U1I-CLK7,_DIFFCLK_3n-Pad88)") (class "Default")
      (node (ref "U1") (pin "88") (pinfunction "CLK7,_DIFFCLK_3n_88") (pintype "input"))
    )
    (net (code "93") (name "unconnected-(U3-NC-Pad3)") (class "Default")
      (node (ref "U3") (pin "3") (pinfunction "NC_3") (pintype "passive"))
    )
    (net (code "94") (name "unconnected-(U3-NC-Pad4)") (class "Default")
      (node (ref "U3") (pin "4") (pinfunction "NC_4") (pintype "passive"))
    )
    (net (code "95") (name "unconnected-(U3-NC-Pad5)") (class "Default")
      (node (ref "U3") (pin "5") (pinfunction "NC_5") (pintype "passive"))
    )
    (net (code "96") (name "unconnected-(U3-NC-Pad6)") (class "Default")
      (node (ref "U3") (pin "6") (pinfunction "NC_6") (pintype "passive"))
    )
    (net (code "97") (name "unconnected-(U3-NC-Pad11)") (class "Default")
      (node (ref "U3") (pin "11") (pinfunction "NC_11") (pintype "passive"))
    )
    (net (code "98") (name "unconnected-(U3-NC-Pad12)") (class "Default")
      (node (ref "U3") (pin "12") (pinfunction "NC_12") (pintype "passive"))
    )
    (net (code "99") (name "unconnected-(U3-NC-Pad13)") (class "Default")
      (node (ref "U3") (pin "13") (pinfunction "NC_13") (pintype "passive"))
    )
    (net (code "100") (name "unconnected-(U3-NC-Pad14)") (class "Default")
      (node (ref "U3") (pin "14") (pinfunction "NC_14") (pintype "passive"))
    )
    (net (code "101") (name "unconnected-(U4-ctrl-Pad1)") (class "Default")
      (node (ref "U4") (pin "1") (pinfunction "ctrl_1") (pintype "passive"))
    )
    (net (code "102") (name "unconnected-(U5-Vout-Pad4)") (class "Default")
      (node (ref "U5") (pin "4") (pinfunction "Vout_4") (pintype "passive"))
    )
    (net (code "103") (name "unconnected-(U6-Vout-Pad4)") (class "Default")
      (node (ref "U6") (pin "4") (pinfunction "Vout_4") (pintype "passive"))
    )
    (net (code "104") (name "unconnected-(U7-Vout-Pad4)") (class "Default")
      (node (ref "U7") (pin "4") (pinfunction "Vout_4") (pintype "passive"))
    )
  )
)
